# USB_Hub_IC.net
KiCad netlist of a schematic drawn in Altium Designer
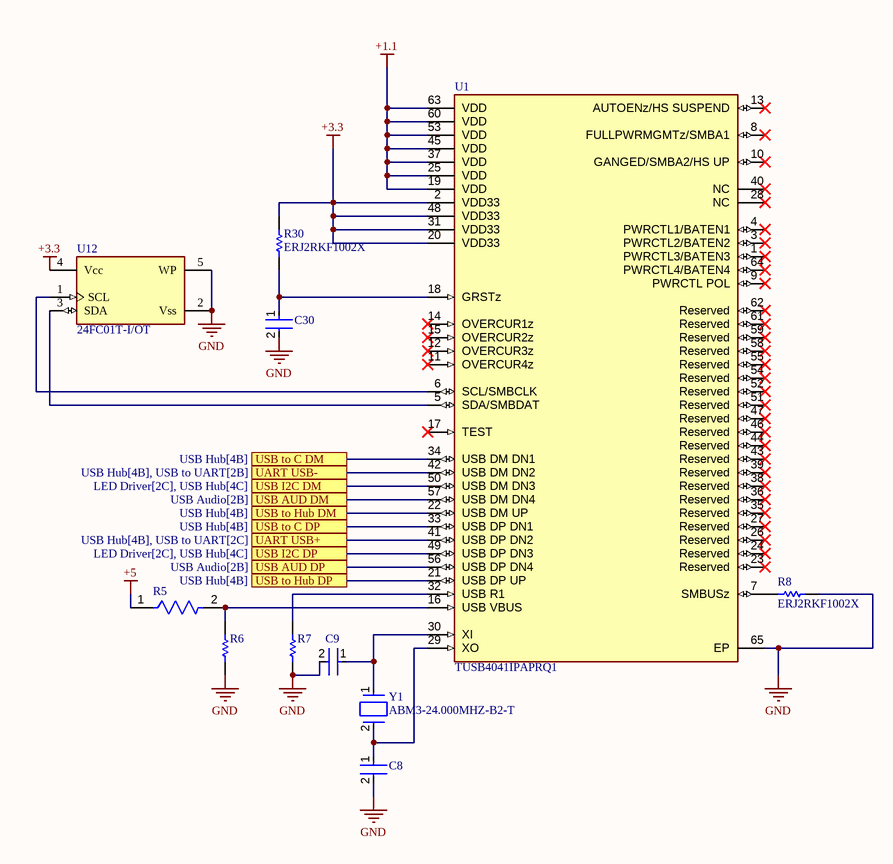
[diagram p0: USB Hub IC.SchDoc]

(export (version "E")
  (design (tool "Eeschema 10.0.6"))
  (components
    (comp (ref "C8")
      (value "GJM1555C1H180JB01D")
      (footprint "FP-GJM155-0_05-IPC_B")
      (description "Multi-Layer Ceramic Capacitor 18pF C0G  ±5% 0402 Paper T/R")
      (fields (field (name "VOLTAGE") "50V") (field (name "TOLERANCE") "5%"))
      (libsource (lib "Altium Content Vault") (part "02cd4be3c70576c341d710602a673aa"))
    )
    (comp (ref "C9")
      (value "GJM1555C1H180JB01D")
      (footprint "FP-GJM155-0_05-IPC_B")
      (description "Multi-Layer Ceramic Capacitor 18pF C0G  ±5% 0402 Paper T/R")
      (fields (field (name "VOLTAGE") "50V") (field (name "TOLERANCE") "5%"))
      (libsource (lib "Altium Content Vault") (part "02cd4be3c70576c341d710602a673aa"))
    )
    (comp (ref "C30")
      (value "GRM1555C1E103GE01D")
      (footprint "FP-GRM155-0_15-IPC_B")
      (description "Chip Multilayer Ceramic Capacitors for General Purpose, 0402, 10000pF, C0G, 30ppm/°C, 2%, 25V")
      (libsource (lib "Altium Content Vault") (part "b4654b650e69147ec39a6b967a45e02"))
    )
    (comp (ref "R5")
      (value "ERJ-2RKF9092X")
      (footprint "FP-ERJ2RK-MFG")
      (description "RES SMD 90.9K OHM 1% 1/10W 0402")
      (fields (field (name "TOLERANCE") "1%"))
      (libsource (lib "Altium Content Vault") (part "1029c3af85768c4190bb7ad29bc67b5"))
    )
    (comp (ref "R6")
      (value "ERJ2RKF1002X")
      (footprint "RESC1005X40X25LL05T05")
      (description "Chip Resistor, 10 KOhm, +/- 1%, 0.1 W, -55 to 155 degC, 0402 (1005 Metric), RoHS, Tape and Reel")
      (fields (field (name "TOLERANCE") "1%") (field (name "MANUFACTURER") "Panasonic"))
      (libsource (lib "Altium Content Vault") (part "RES-2"))
    )
    (comp (ref "R7")
      (value "ERA-3AED9531V")
      (footprint "RESC1608X55X30ML20T20")
      (fields (field (name "MANUFACTURER") "Panasonic"))
      (libsource (lib "Altium Content Vault") (part "RES"))
    )
    (comp (ref "R8")
      (value "ERJ2RKF1002X")
      (footprint "RESC1005X40X25LL05T05")
      (description "Chip Resistor, 10 KOhm, +/- 1%, 0.1 W, -55 to 155 degC, 0402 (1005 Metric), RoHS, Tape and Reel")
      (fields (field (name "TOLERANCE") "1%") (field (name "MANUFACTURER") "Panasonic"))
      (libsource (lib "Altium Content Vault") (part "RES-2"))
    )
    (comp (ref "R30")
      (value "ERJ2RKF1002X")
      (footprint "RESC1005X40X25LL05T05")
      (description "Chip Resistor, 10 KOhm, +/- 1%, 0.1 W, -55 to 155 degC, 0402 (1005 Metric), RoHS, Tape and Reel")
      (fields (field (name "TOLERANCE") "1%") (field (name "MANUFACTURER") "Panasonic"))
      (libsource (lib "Altium Content Vault") (part "RES-2"))
    )
    (comp (ref "U1")
      (value "TUSB4041IPAPRQ1")
      (footprint "FP-PAP0064K-MFG")
      (description "IC USB 2.0 4PORT HUB 64HTQFP")
      (fields
        (field (name "MANUFACTURER") "Texas Instruments")
        (field (name "MANUFACTURER PART NUMBER") "TUSB4041IPAPR")
      )
      (libsource (lib "Altium Content Vault") (part "5e978d452e673cf9c6e58b86f9ac1bd"))
    )
    (comp (ref "U12")
      (value "24FC01T-I/OT")
      (footprint "FP-C04-091-OT-MFG")
      (description "IC EEPROM 1KBIT I2C 1MHZ SOT23-5")
      (libsource (lib "Altium Content Vault") (part "ee34ec4cceb221c3c7608d5f38ce5d4"))
    )
    (comp (ref "Y1")
      (value "ABM3-24.000MHZ-B2-T")
      (footprint "FP-ABM3-MFG")
      (description "Crystal 24MHz ±20ppm 18pF SMD-2 5mm x 3.2mm")
      (fields (field (name "TOLERANCE") "20ppm"))
      (libsource (lib "Altium Content Vault") (part "c23a69dc6c9e2f18f2079038eb95dd1"))
    )
  )
  (nets
    (net (code "1") (name "+1.1") (class "Default")
      (node (ref "U1") (pin "19") (pinfunction "VDD_19") (pintype "power_in"))
      (node (ref "U1") (pin "25") (pinfunction "VDD_25") (pintype "power_in"))
      (node (ref "U1") (pin "37") (pinfunction "VDD_37") (pintype "power_in"))
      (node (ref "U1") (pin "45") (pinfunction "VDD_45") (pintype "power_in"))
      (node (ref "U1") (pin "53") (pinfunction "VDD_53") (pintype "power_in"))
      (node (ref "U1") (pin "60") (pinfunction "VDD_60") (pintype "power_in"))
      (node (ref "U1") (pin "63") (pinfunction "VDD_63") (pintype "power_in"))
    )
    (net (code "2") (name "+3.3") (class "Default")
      (node (ref "R30") (pin "2") (pinfunction "2_2") (pintype "passive"))
      (node (ref "U1") (pin "2") (pinfunction "VDD33_2") (pintype "power_in"))
      (node (ref "U1") (pin "20") (pinfunction "VDD33_20") (pintype "power_in"))
      (node (ref "U1") (pin "31") (pinfunction "VDD33_31") (pintype "power_in"))
      (node (ref "U1") (pin "48") (pinfunction "VDD33_48") (pintype "power_in"))
      (node (ref "U12") (pin "4") (pinfunction "Vcc_4") (pintype "power_in"))
    )
    (net (code "3") (name "+5") (class "Default")
      (node (ref "R5") (pin "1") (pinfunction "1_1") (pintype "passive"))
    )
    (net (code "4") (name "/UART USB+") (class "Default")
      (node (ref "U1") (pin "41") (pinfunction "USB_DP_DN2_41") (pintype "bidirectional"))
    )
    (net (code "5") (name "/UART USB-") (class "Default")
      (node (ref "U1") (pin "42") (pinfunction "USB_DM_DN2_42") (pintype "bidirectional"))
    )
    (net (code "6") (name "/USB AUD DM") (class "Default")
      (node (ref "U1") (pin "57") (pinfunction "USB_DM_DN4_57") (pintype "bidirectional"))
    )
    (net (code "7") (name "/USB AUD DP") (class "Default")
      (node (ref "U1") (pin "56") (pinfunction "USB_DP_DN4_56") (pintype "bidirectional"))
    )
    (net (code "8") (name "/USB I2C DM") (class "Default")
      (node (ref "U1") (pin "50") (pinfunction "USB_DM_DN3_50") (pintype "bidirectional"))
    )
    (net (code "9") (name "/USB I2C DP") (class "Default")
      (node (ref "U1") (pin "49") (pinfunction "USB_DP_DN3_49") (pintype "bidirectional"))
    )
    (net (code "10") (name "/USB to C DM") (class "Default")
      (node (ref "U1") (pin "34") (pinfunction "USB_DM_DN1_34") (pintype "bidirectional"))
    )
    (net (code "11") (name "/USB to C DP") (class "Default")
      (node (ref "U1") (pin "33") (pinfunction "USB_DP_DN1_33") (pintype "bidirectional"))
    )
    (net (code "12") (name "/USB to Hub DM") (class "Default")
      (node (ref "U1") (pin "22") (pinfunction "USB_DM_UP_22") (pintype "bidirectional"))
    )
    (net (code "13") (name "/USB to Hub DP") (class "Default")
      (node (ref "U1") (pin "21") (pinfunction "USB_DP_UP_21") (pintype "bidirectional"))
    )
    (net (code "14") (name "GND") (class "Default")
      (node (ref "C30") (pin "2") (pinfunction "2_2") (pintype "passive"))
      (node (ref "C8") (pin "2") (pinfunction "2_2") (pintype "passive"))
      (node (ref "C9") (pin "2") (pinfunction "2_2") (pintype "passive"))
      (node (ref "R6") (pin "1") (pinfunction "1_1") (pintype "passive"))
      (node (ref "R7") (pin "1") (pinfunction "1_1") (pintype "passive"))
      (node (ref "R8") (pin "1") (pinfunction "1_1") (pintype "passive"))
      (node (ref "U1") (pin "65") (pinfunction "EP_65") (pintype "power_in"))
      (node (ref "U12") (pin "2") (pinfunction "Vss_2") (pintype "power_in"))
      (node (ref "U12") (pin "5") (pinfunction "WP_5") (pintype "passive"))
    )
    (net (code "15") (name "Net-(U1-GRSTz)") (class "Default")
      (node (ref "C30") (pin "1") (pinfunction "1_1") (pintype "passive"))
      (node (ref "R30") (pin "1") (pinfunction "1_1") (pintype "passive"))
      (node (ref "U1") (pin "18") (pinfunction "GRSTz_18") (pintype "input"))
    )
    (net (code "16") (name "Net-(U1-SCL{slash}SMBCLK)") (class "Default")
      (node (ref "U1") (pin "6") (pinfunction "SCL/SMBCLK_6") (pintype "bidirectional"))
      (node (ref "U12") (pin "1") (pinfunction "SCL_1") (pintype "input"))
    )
    (net (code "17") (name "Net-(U1-SDA{slash}SMBDAT)") (class "Default")
      (node (ref "U1") (pin "5") (pinfunction "SDA/SMBDAT_5") (pintype "bidirectional"))
      (node (ref "U12") (pin "3") (pinfunction "SDA_3") (pintype "bidirectional"))
    )
    (net (code "18") (name "Net-(U1-SMBUSz)") (class "Default")
      (node (ref "R8") (pin "2") (pinfunction "2_2") (pintype "passive"))
      (node (ref "U1") (pin "7") (pinfunction "SMBUSz_7") (pintype "bidirectional"))
    )
    (net (code "19") (name "Net-(U1-USB_R1)") (class "Default")
      (node (ref "R7") (pin "2") (pinfunction "2_2") (pintype "passive"))
      (node (ref "U1") (pin "32") (pinfunction "USB_R1_32") (pintype "input"))
    )
    (net (code "20") (name "Net-(U1-USB_VBUS)") (class "Default")
      (node (ref "R5") (pin "2") (pinfunction "2_2") (pintype "passive"))
      (node (ref "R6") (pin "2") (pinfunction "2_2") (pintype "passive"))
      (node (ref "U1") (pin "16") (pinfunction "USB_VBUS_16") (pintype "input"))
    )
    (net (code "21") (name "Net-(U1-XI)") (class "Default")
      (node (ref "C9") (pin "1") (pinfunction "1_1") (pintype "passive"))
      (node (ref "U1") (pin "30") (pinfunction "XI_30") (pintype "input"))
      (node (ref "Y1") (pin "1") (pinfunction "1_1") (pintype "passive"))
    )
    (net (code "22") (name "Net-(U1-XO)") (class "Default")
      (node (ref "C8") (pin "1") (pinfunction "1_1") (pintype "passive"))
      (node (ref "U1") (pin "29") (pinfunction "XO_29") (pintype "input"))
      (node (ref "Y1") (pin "2") (pinfunction "2_2") (pintype "passive"))
    )
    (net (code "23") (name "unconnected-(U1-AUTOENz{slash}HS_SUSPEND-Pad13)") (class "Default")
      (node (ref "U1") (pin "13") (pinfunction "AUTOENz/HS_SUSPEND_13") (pintype "bidirectional+no_connect"))
    )
    (net (code "24") (name "unconnected-(U1-FULLPWRMGMTz{slash}SMBA1-Pad8)") (class "Default")
      (node (ref "U1") (pin "8") (pinfunction "FULLPWRMGMTz/SMBA1_8") (pintype "bidirectional+no_connect"))
    )
    (net (code "25") (name "unconnected-(U1-GANGED{slash}SMBA2{slash}HS_UP-Pad10)") (class "Default")
      (node (ref "U1") (pin "10") (pinfunction "GANGED/SMBA2/HS_UP_10") (pintype "bidirectional+no_connect"))
    )
    (net (code "26") (name "unconnected-(U1-NC-Pad28)") (class "Default")
      (node (ref "U1") (pin "28") (pinfunction "NC_28") (pintype "passive+no_connect"))
    )
    (net (code "27") (name "unconnected-(U1-NC-Pad40)") (class "Default")
      (node (ref "U1") (pin "40") (pinfunction "NC_40") (pintype "passive+no_connect"))
    )
    (net (code "28") (name "unconnected-(U1-OVERCUR1z-Pad14)") (class "Default")
      (node (ref "U1") (pin "14") (pinfunction "OVERCUR1z_14") (pintype "input+no_connect"))
    )
    (net (code "29") (name "unconnected-(U1-OVERCUR2z-Pad15)") (class "Default")
      (node (ref "U1") (pin "15") (pinfunction "OVERCUR2z_15") (pintype "input+no_connect"))
    )
    (net (code "30") (name "unconnected-(U1-OVERCUR3z-Pad12)") (class "Default")
      (node (ref "U1") (pin "12") (pinfunction "OVERCUR3z_12") (pintype "input+no_connect"))
    )
    (net (code "31") (name "unconnected-(U1-OVERCUR4z-Pad11)") (class "Default")
      (node (ref "U1") (pin "11") (pinfunction "OVERCUR4z_11") (pintype "input+no_connect"))
    )
    (net (code "32") (name "unconnected-(U1-PWRCTL1{slash}BATEN1-Pad4)") (class "Default")
      (node (ref "U1") (pin "4") (pinfunction "PWRCTL1/BATEN1_4") (pintype "bidirectional+no_connect"))
    )
    (net (code "33") (name "unconnected-(U1-PWRCTL2{slash}BATEN2-Pad3)") (class "Default")
      (node (ref "U1") (pin "3") (pinfunction "PWRCTL2/BATEN2_3") (pintype "bidirectional+no_connect"))
    )
    (net (code "34") (name "unconnected-(U1-PWRCTL3{slash}BATEN3-Pad1)") (class "Default")
      (node (ref "U1") (pin "1") (pinfunction "PWRCTL3/BATEN3_1") (pintype "bidirectional+no_connect"))
    )
    (net (code "35") (name "unconnected-(U1-PWRCTL4{slash}BATEN4-Pad64)") (class "Default")
      (node (ref "U1") (pin "64") (pinfunction "PWRCTL4/BATEN4_64") (pintype "bidirectional+no_connect"))
    )
    (net (code "36") (name "unconnected-(U1-PWRCTL_POL-Pad9)") (class "Default")
      (node (ref "U1") (pin "9") (pinfunction "PWRCTL_POL_9") (pintype "bidirectional+no_connect"))
    )
    (net (code "37") (name "unconnected-(U1-Reserved-Pad23)") (class "Default")
      (node (ref "U1") (pin "23") (pinfunction "Reserved_23") (pintype "bidirectional+no_connect"))
    )
    (net (code "38") (name "unconnected-(U1-Reserved-Pad24)") (class "Default")
      (node (ref "U1") (pin "24") (pinfunction "Reserved_24") (pintype "bidirectional+no_connect"))
    )
    (net (code "39") (name "unconnected-(U1-Reserved-Pad26)") (class "Default")
      (node (ref "U1") (pin "26") (pinfunction "Reserved_26") (pintype "bidirectional+no_connect"))
    )
    (net (code "40") (name "unconnected-(U1-Reserved-Pad27)") (class "Default")
      (node (ref "U1") (pin "27") (pinfunction "Reserved_27") (pintype "bidirectional+no_connect"))
    )
    (net (code "41") (name "unconnected-(U1-Reserved-Pad35)") (class "Default")
      (node (ref "U1") (pin "35") (pinfunction "Reserved_35") (pintype "bidirectional+no_connect"))
    )
    (net (code "42") (name "unconnected-(U1-Reserved-Pad36)") (class "Default")
      (node (ref "U1") (pin "36") (pinfunction "Reserved_36") (pintype "bidirectional+no_connect"))
    )
    (net (code "43") (name "unconnected-(U1-Reserved-Pad38)") (class "Default")
      (node (ref "U1") (pin "38") (pinfunction "Reserved_38") (pintype "bidirectional+no_connect"))
    )
    (net (code "44") (name "unconnected-(U1-Reserved-Pad39)") (class "Default")
      (node (ref "U1") (pin "39") (pinfunction "Reserved_39") (pintype "bidirectional+no_connect"))
    )
    (net (code "45") (name "unconnected-(U1-Reserved-Pad43)") (class "Default")
      (node (ref "U1") (pin "43") (pinfunction "Reserved_43") (pintype "bidirectional+no_connect"))
    )
    (net (code "46") (name "unconnected-(U1-Reserved-Pad44)") (class "Default")
      (node (ref "U1") (pin "44") (pinfunction "Reserved_44") (pintype "bidirectional+no_connect"))
    )
    (net (code "47") (name "unconnected-(U1-Reserved-Pad46)") (class "Default")
      (node (ref "U1") (pin "46") (pinfunction "Reserved_46") (pintype "bidirectional+no_connect"))
    )
    (net (code "48") (name "unconnected-(U1-Reserved-Pad47)") (class "Default")
      (node (ref "U1") (pin "47") (pinfunction "Reserved_47") (pintype "bidirectional+no_connect"))
    )
    (net (code "49") (name "unconnected-(U1-Reserved-Pad51)") (class "Default")
      (node (ref "U1") (pin "51") (pinfunction "Reserved_51") (pintype "bidirectional+no_connect"))
    )
    (net (code "50") (name "unconnected-(U1-Reserved-Pad52)") (class "Default")
      (node (ref "U1") (pin "52") (pinfunction "Reserved_52") (pintype "bidirectional+no_connect"))
    )
    (net (code "51") (name "unconnected-(U1-Reserved-Pad54)") (class "Default")
      (node (ref "U1") (pin "54") (pinfunction "Reserved_54") (pintype "bidirectional+no_connect"))
    )
    (net (code "52") (name "unconnected-(U1-Reserved-Pad55)") (class "Default")
      (node (ref "U1") (pin "55") (pinfunction "Reserved_55") (pintype "bidirectional+no_connect"))
    )
    (net (code "53") (name "unconnected-(U1-Reserved-Pad58)") (class "Default")
      (node (ref "U1") (pin "58") (pinfunction "Reserved_58") (pintype "bidirectional+no_connect"))
    )
    (net (code "54") (name "unconnected-(U1-Reserved-Pad59)") (class "Default")
      (node (ref "U1") (pin "59") (pinfunction "Reserved_59") (pintype "bidirectional+no_connect"))
    )
    (net (code "55") (name "unconnected-(U1-Reserved-Pad61)") (class "Default")
      (node (ref "U1") (pin "61") (pinfunction "Reserved_61") (pintype "bidirectional+no_connect"))
    )
    (net (code "56") (name "unconnected-(U1-Reserved-Pad62)") (class "Default")
      (node (ref "U1") (pin "62") (pinfunction "Reserved_62") (pintype "bidirectional+no_connect"))
    )
    (net (code "57") (name "unconnected-(U1-TEST-Pad17)") (class "Default")
      (node (ref "U1") (pin "17") (pinfunction "TEST_17") (pintype "input+no_connect"))
    )
  )
)
